# joystickschematic.net
KiCad netlist of a schematic drawn in EAGLE
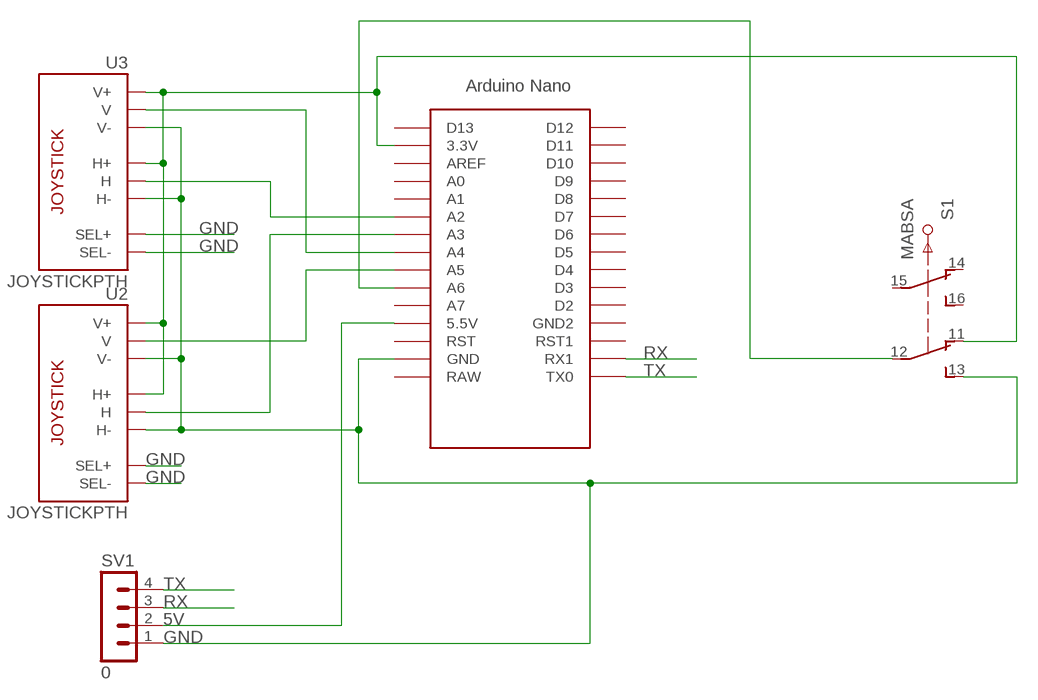
[diagram p0: schematic, sheet 1]

(export (version "E")
  (design (tool "Eeschema 10.0.6"))
  (components
    (comp (ref "S1")
      (value "MABSA")
      (footprint "eagle-import:MABSA")
      (libsource (lib "eagle-import") (part "MABSA"))
    )
    (comp (ref "SV1")
      (value "0")
      (footprint "eagle-import:MA04-1")
      (libsource (lib "eagle-import") (part "MA04-1"))
    )
    (comp (ref "U$2")
      (value "NANO")
      (footprint "eagle-import:NANO")
      (libsource (lib "eagle-import") (part "NANO"))
    )
    (comp (ref "U2")
      (value "JOYSTICKPTH")
      (footprint "eagle-import:JOYSTICK")
      (libsource (lib "eagle-import") (part "JOYSTICKPTH"))
    )
    (comp (ref "U3")
      (value "JOYSTICKPTH")
      (footprint "eagle-import:JOYSTICK")
      (libsource (lib "eagle-import") (part "JOYSTICKPTH"))
    )
  )
  (nets
    (net (code "1") (name "/5V") (class "Default")
      (node (ref "SV1") (pin "2") (pinfunction "2_2") (pintype "passive"))
      (node (ref "U$2") (pin "5V") (pinfunction "5.5V_5V") (pintype "bidirectional"))
    )
    (net (code "2") (name "/GND") (class "Default")
      (node (ref "S1") (pin "13") (pinfunction "13_13") (pintype "passive"))
      (node (ref "SV1") (pin "1") (pinfunction "1_1") (pintype "passive"))
      (node (ref "U$2") (pin "GND") (pinfunction "GND_GND") (pintype "bidirectional"))
      (node (ref "U2") (pin "B1A") (pinfunction "SEL+_B1A") (pintype "bidirectional"))
      (node (ref "U2") (pin "B2A") (pinfunction "SEL-_B2A") (pintype "bidirectional"))
      (node (ref "U2") (pin "H3") (pinfunction "H-_H3") (pintype "bidirectional"))
      (node (ref "U2") (pin "V3") (pinfunction "V-_V3") (pintype "bidirectional"))
      (node (ref "U3") (pin "B1A") (pinfunction "SEL+_B1A") (pintype "bidirectional"))
      (node (ref "U3") (pin "B2A") (pinfunction "SEL-_B2A") (pintype "bidirectional"))
      (node (ref "U3") (pin "H3") (pinfunction "H-_H3") (pintype "bidirectional"))
      (node (ref "U3") (pin "V3") (pinfunction "V-_V3") (pintype "bidirectional"))
    )
    (net (code "3") (name "/RX") (class "Default")
      (node (ref "SV1") (pin "3") (pinfunction "3_3") (pintype "passive"))
      (node (ref "U$2") (pin "RX1") (pinfunction "RX1_RX1") (pintype "bidirectional"))
    )
    (net (code "4") (name "/TX") (class "Default")
      (node (ref "SV1") (pin "4") (pinfunction "4_4") (pintype "passive"))
      (node (ref "U$2") (pin "TX0") (pinfunction "TX0_TX0") (pintype "bidirectional"))
    )
    (net (code "5") (name "Net-(S1-Pad12)") (class "Default")
      (node (ref "S1") (pin "12") (pinfunction "12_12") (pintype "passive"))
      (node (ref "U$2") (pin "A6") (pinfunction "A6_A6") (pintype "bidirectional"))
    )
    (net (code "6") (name "Net-(U2-H)") (class "Default")
      (node (ref "U$2") (pin "A3") (pinfunction "A3_A3") (pintype "bidirectional"))
      (node (ref "U2") (pin "H2") (pinfunction "H_H2") (pintype "bidirectional"))
    )
    (net (code "7") (name "Net-(U2-H+)") (class "Default")
      (node (ref "S1") (pin "11") (pinfunction "11_11") (pintype "passive"))
      (node (ref "U$2") (pin "3.3V") (pinfunction "3.3V_3.3V") (pintype "bidirectional"))
      (node (ref "U2") (pin "H1") (pinfunction "H+_H1") (pintype "bidirectional"))
      (node (ref "U2") (pin "V1") (pinfunction "V+_V1") (pintype "bidirectional"))
      (node (ref "U3") (pin "H1") (pinfunction "H+_H1") (pintype "bidirectional"))
      (node (ref "U3") (pin "V1") (pinfunction "V+_V1") (pintype "bidirectional"))
    )
    (net (code "8") (name "Net-(U2-V)") (class "Default")
      (node (ref "U$2") (pin "A5") (pinfunction "A5_A5") (pintype "bidirectional"))
      (node (ref "U2") (pin "V2") (pinfunction "V_V2") (pintype "bidirectional"))
    )
    (net (code "9") (name "Net-(U3-H)") (class "Default")
      (node (ref "U$2") (pin "A2") (pinfunction "A2_A2") (pintype "bidirectional"))
      (node (ref "U3") (pin "H2") (pinfunction "H_H2") (pintype "bidirectional"))
    )
    (net (code "10") (name "Net-(U3-V)") (class "Default")
      (node (ref "U$2") (pin "A4") (pinfunction "A4_A4") (pintype "bidirectional"))
      (node (ref "U3") (pin "V2") (pinfunction "V_V2") (pintype "bidirectional"))
    )
    (net (code "11") (name "unconnected-(S1-Pad14)") (class "Default")
      (node (ref "S1") (pin "14") (pinfunction "14_14") (pintype "passive"))
    )
    (net (code "12") (name "unconnected-(S1-Pad15)") (class "Default")
      (node (ref "S1") (pin "15") (pinfunction "15_15") (pintype "passive"))
    )
    (net (code "13") (name "unconnected-(S1-Pad16)") (class "Default")
      (node (ref "S1") (pin "16") (pinfunction "16_16") (pintype "passive"))
    )
    (net (code "14") (name "unconnected-(U$2-GND2-PadGND1)") (class "Default")
      (node (ref "U$2") (pin "GND1") (pinfunction "GND2_GND1") (pintype "bidirectional"))
    )
    (net (code "15") (name "unconnected-(U$2-PadA0)") (class "Default")
      (node (ref "U$2") (pin "A0") (pinfunction "A0_A0") (pintype "bidirectional"))
    )
    (net (code "16") (name "unconnected-(U$2-PadA1)") (class "Default")
      (node (ref "U$2") (pin "A1") (pinfunction "A1_A1") (pintype "bidirectional"))
    )
    (net (code "17") (name "unconnected-(U$2-PadA7)") (class "Default")
      (node (ref "U$2") (pin "A7") (pinfunction "A7_A7") (pintype "bidirectional"))
    )
    (net (code "18") (name "unconnected-(U$2-PadAREF)") (class "Default")
      (node (ref "U$2") (pin "AREF") (pinfunction "AREF_AREF") (pintype "bidirectional"))
    )
    (net (code "19") (name "unconnected-(U$2-PadD2)") (class "Default")
      (node (ref "U$2") (pin "D2") (pinfunction "D2_D2") (pintype "bidirectional"))
    )
    (net (code "20") (name "unconnected-(U$2-PadD3)") (class "Default")
      (node (ref "U$2") (pin "D3") (pinfunction "D3_D3") (pintype "bidirectional"))
    )
    (net (code "21") (name "unconnected-(U$2-PadD4)") (class "Default")
      (node (ref "U$2") (pin "D4") (pinfunction "D4_D4") (pintype "bidirectional"))
    )
    (net (code "22") (name "unconnected-(U$2-PadD5)") (class "Default")
      (node (ref "U$2") (pin "D5") (pinfunction "D5_D5") (pintype "bidirectional"))
    )
    (net (code "23") (name "unconnected-(U$2-PadD6)") (class "Default")
      (node (ref "U$2") (pin "D6") (pinfunction "D6_D6") (pintype "bidirectional"))
    )
    (net (code "24") (name "unconnected-(U$2-PadD7)") (class "Default")
      (node (ref "U$2") (pin "D7") (pinfunction "D7_D7") (pintype "bidirectional"))
    )
    (net (code "25") (name "unconnected-(U$2-PadD8)") (class "Default")
      (node (ref "U$2") (pin "D8") (pinfunction "D8_D8") (pintype "bidirectional"))
    )
    (net (code "26") (name "unconnected-(U$2-PadD9)") (class "Default")
      (node (ref "U$2") (pin "D9") (pinfunction "D9_D9") (pintype "bidirectional"))
    )
    (net (code "27") (name "unconnected-(U$2-PadD10)") (class "Default")
      (node (ref "U$2") (pin "D10") (pinfunction "D10_D10") (pintype "bidirectional"))
    )
    (net (code "28") (name "unconnected-(U$2-PadD11)") (class "Default")
      (node (ref "U$2") (pin "D11") (pinfunction "D11_D11") (pintype "bidirectional"))
    )
    (net (code "29") (name "unconnected-(U$2-PadD12)") (class "Default")
      (node (ref "U$2") (pin "D12") (pinfunction "D12_D12") (pintype "bidirectional"))
    )
    (net (code "30") (name "unconnected-(U$2-PadD13)") (class "Default")
      (node (ref "U$2") (pin "D13") (pinfunction "D13_D13") (pintype "bidirectional"))
    )
    (net (code "31") (name "unconnected-(U$2-PadRAW)") (class "Default")
      (node (ref "U$2") (pin "RAW") (pinfunction "RAW_RAW") (pintype "bidirectional"))
    )
    (net (code "32") (name "unconnected-(U$2-PadRST)") (class "Default")
      (node (ref "U$2") (pin "RST") (pinfunction "RST_RST") (pintype "bidirectional"))
    )
    (net (code "33") (name "unconnected-(U$2-PadRST1)") (class "Default")
      (node (ref "U$2") (pin "RST1") (pinfunction "RST1_RST1") (pintype "bidirectional"))
    )
  )
)
